# trackuino_micro_sensor.net
KiCad netlist of a schematic drawn in EAGLE
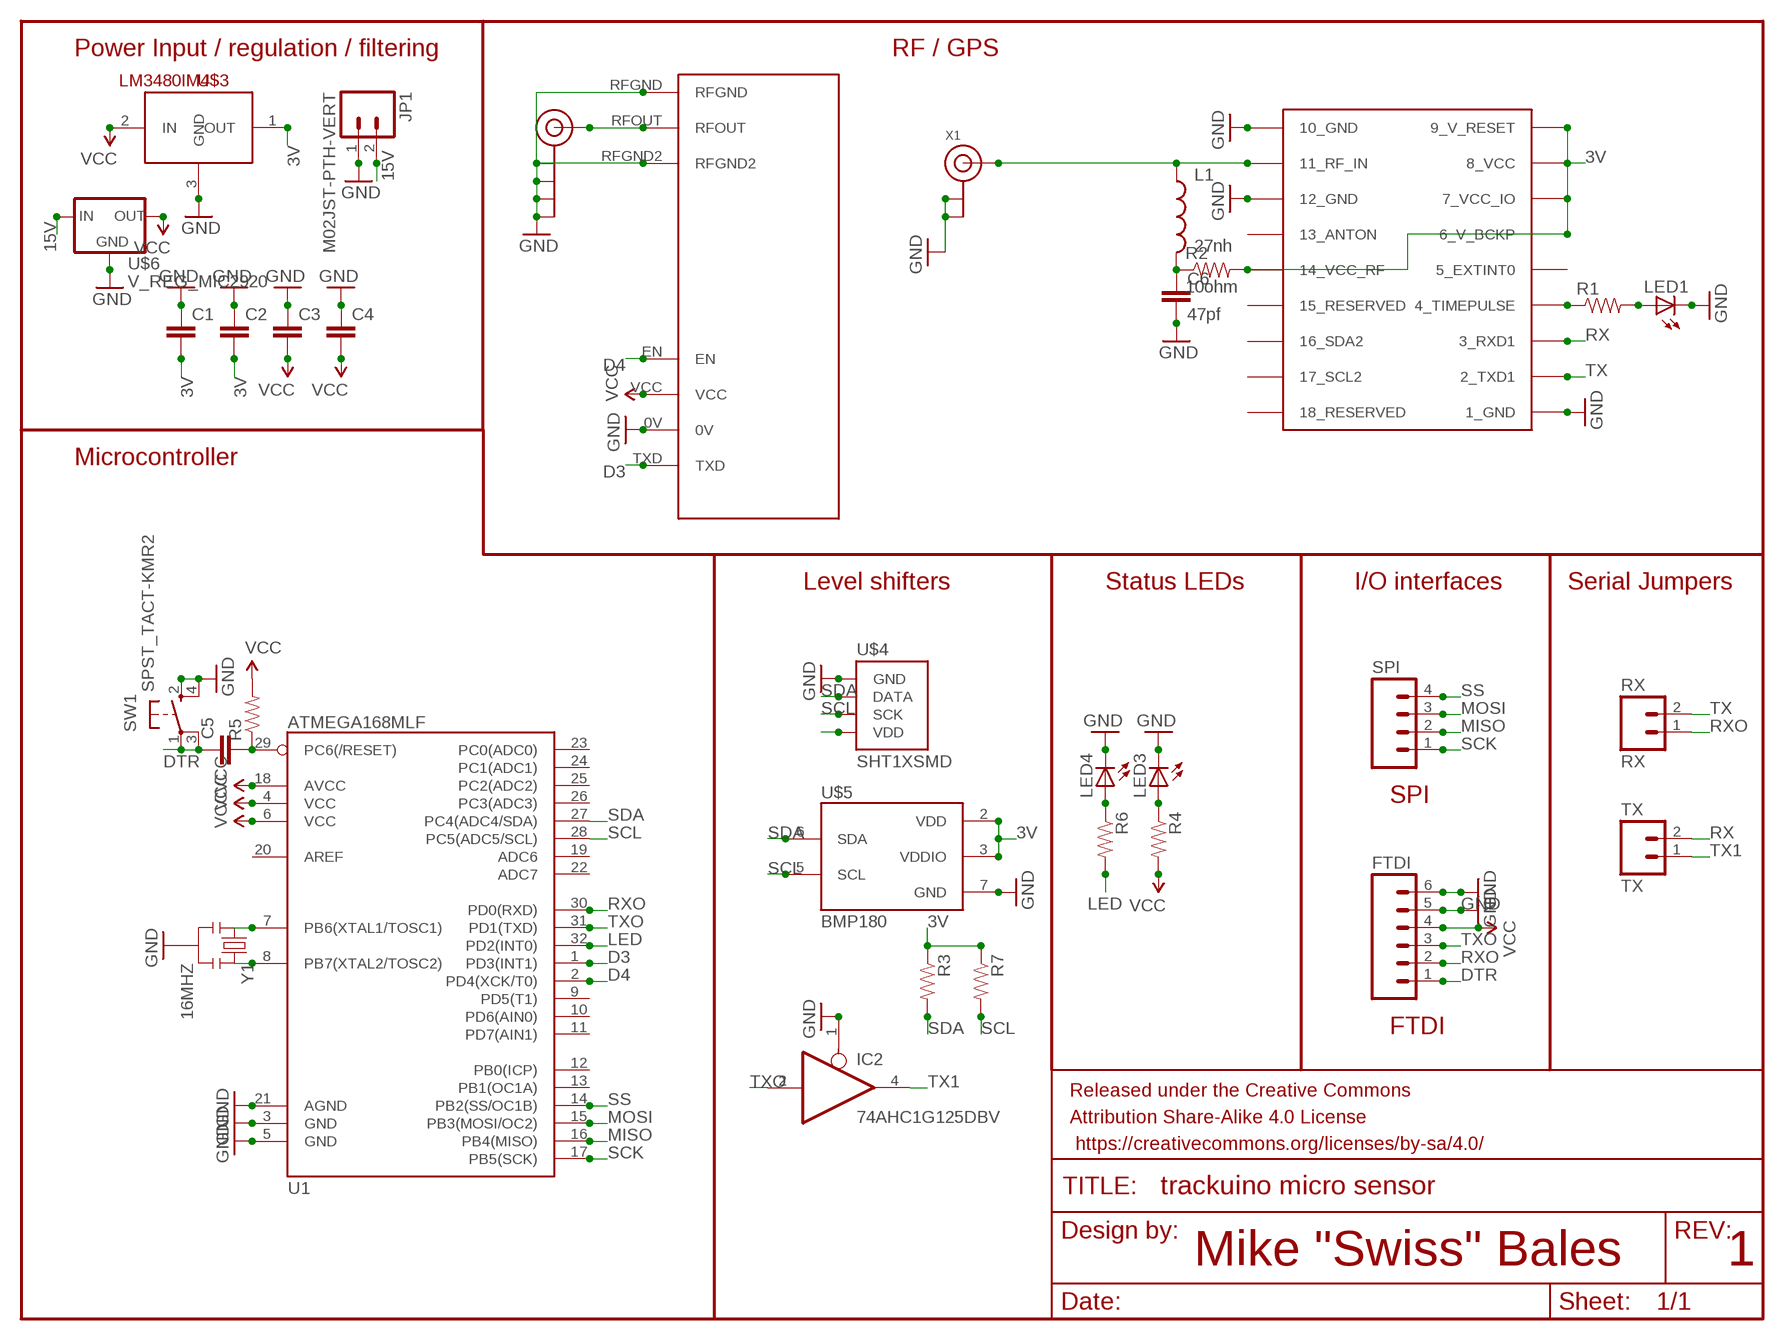
[diagram p0: schematic, sheet 1]

(export (version "E")
  (design (tool "Eeschema 10.0.6"))
  (components
    (comp (ref "C1")
      (value "CAP0805")
      (footprint "eagle-import:0805")
      (libsource (lib "eagle-import") (part "CAP0805"))
    )
    (comp (ref "C2")
      (value "CAP0805")
      (footprint "eagle-import:0805")
      (libsource (lib "eagle-import") (part "CAP0805"))
    )
    (comp (ref "C3")
      (value "CAP0805")
      (footprint "eagle-import:0805")
      (libsource (lib "eagle-import") (part "CAP0805"))
    )
    (comp (ref "C4")
      (value "CAP0805")
      (footprint "eagle-import:0805")
      (libsource (lib "eagle-import") (part "CAP0805"))
    )
    (comp (ref "C5")
      (value "CAP0805")
      (footprint "eagle-import:0805")
      (libsource (lib "eagle-import") (part "CAP0805"))
    )
    (comp (ref "C6")
      (value "47pf")
      (footprint "eagle-import:0805")
      (libsource (lib "eagle-import") (part "CAP0805"))
    )
    (comp (ref "FRAME1")
      (value "FRAME-LETTER")
      (footprint "eagle-import:CREATIVE_COMMONS")
      (libsource (lib "eagle-import") (part "FRAME-LETTER"))
    )
    (comp (ref "FTDI")
      (value "M06NO_SILK_FEMALE_PTH")
      (footprint "eagle-import:1X06_NO_SILK")
      (libsource (lib "eagle-import") (part "M06NO_SILK_FEMALE_PTH"))
    )
    (comp (ref "IC2")
      (value "74AHC1G125DBV")
      (footprint "eagle-import:SOT23-5")
      (libsource (lib "eagle-import") (part "741G125DBVAHC"))
    )
    (comp (ref "J$1")
      (value "SMA_EDGE")
      (footprint "eagle-import:SMA-EDGE")
      (libsource (lib "eagle-import") (part "SMA_EDGE"))
    )
    (comp (ref "JP1")
      (value "M02JST-PTH-VERT")
      (footprint "eagle-import:JST-2-PTH-VERT")
      (libsource (lib "eagle-import") (part "M02JST-PTH-VERT"))
    )
    (comp (ref "L1")
      (value "27nh")
      (footprint "eagle-import:0805")
      (libsource (lib "eagle-import") (part "INDUCTOR0805"))
    )
    (comp (ref "LED1")
      (value "LEDCHIP-LED0805")
      (footprint "eagle-import:CHIP-LED0805")
      (libsource (lib "eagle-import") (part "LEDCHIP-LED0805"))
    )
    (comp (ref "LED3")
      (value "LEDCHIP-LED0805")
      (footprint "eagle-import:CHIP-LED0805")
      (libsource (lib "eagle-import") (part "LEDCHIP-LED0805"))
    )
    (comp (ref "LED4")
      (value "LEDCHIP-LED0805")
      (footprint "eagle-import:CHIP-LED0805")
      (libsource (lib "eagle-import") (part "LEDCHIP-LED0805"))
    )
    (comp (ref "R1")
      (value "RESISTOR0805-RES")
      (footprint "eagle-import:0805")
      (libsource (lib "eagle-import") (part "RESISTOR0805-RES"))
    )
    (comp (ref "R2")
      (value "10ohm")
      (footprint "eagle-import:0805")
      (libsource (lib "eagle-import") (part "RESISTOR0805-RES"))
    )
    (comp (ref "R3")
      (value "RESISTOR0805-RES")
      (footprint "eagle-import:0805")
      (libsource (lib "eagle-import") (part "RESISTOR0805-RES"))
    )
    (comp (ref "R4")
      (value "RESISTOR0805-RES")
      (footprint "eagle-import:0805")
      (libsource (lib "eagle-import") (part "RESISTOR0805-RES"))
    )
    (comp (ref "R5")
      (value "RESISTOR0805-RES")
      (footprint "eagle-import:0805")
      (libsource (lib "eagle-import") (part "RESISTOR0805-RES"))
    )
    (comp (ref "R6")
      (value "RESISTOR0805-RES")
      (footprint "eagle-import:0805")
      (libsource (lib "eagle-import") (part "RESISTOR0805-RES"))
    )
    (comp (ref "R7")
      (value "RESISTOR0805-RES")
      (footprint "eagle-import:0805")
      (libsource (lib "eagle-import") (part "RESISTOR0805-RES"))
    )
    (comp (ref "RX")
      (value "RX")
      (footprint "eagle-import:1X02")
      (libsource (lib "eagle-import") (part "M02PTH"))
    )
    (comp (ref "SPI")
      (value "M041X04_NO_SILK")
      (footprint "eagle-import:1X04_NO_SILK")
      (libsource (lib "eagle-import") (part "M041X04_NO_SILK"))
    )
    (comp (ref "SW1")
      (value "SPST_TACT-KMR2")
      (footprint "eagle-import:KMR2")
      (libsource (lib "eagle-import") (part "SPST_TACT-KMR2"))
    )
    (comp (ref "TX")
      (value "TX")
      (footprint "eagle-import:1X02")
      (libsource (lib "eagle-import") (part "M02PTH"))
    )
    (comp (ref "U$1")
      (value "UBLOX_MAX")
      (footprint "eagle-import:UBLOX_MAX")
      (libsource (lib "eagle-import") (part "UBLOX_MAX"))
    )
    (comp (ref "U$2")
      (value "RADIOMETRIX-HX1")
      (footprint "eagle-import:RADIOMETRIX-HX1")
      (libsource (lib "eagle-import") (part "RADIOMETRIX-HX1"))
    )
    (comp (ref "U$3")
      (value "LM3480IM4")
      (footprint "eagle-import:SOT23-3")
      (libsource (lib "eagle-import") (part "LM3480IM4"))
    )
    (comp (ref "U$4")
      (value "SHT1XSMD")
      (footprint "eagle-import:SHT1X")
      (libsource (lib "eagle-import") (part "SHT1XSMD"))
    )
    (comp (ref "U$5")
      (value "BMP180")
      (footprint "eagle-import:BMP180")
      (libsource (lib "eagle-import") (part "BMP180"))
    )
    (comp (ref "U$6")
      (value "V_REG_MIC2920")
      (footprint "eagle-import:SOT223")
      (libsource (lib "eagle-import") (part "V_REG_MIC2920"))
    )
    (comp (ref "U1")
      (value "ATMEGA168MLF")
      (footprint "eagle-import:MLF32")
      (libsource (lib "eagle-import") (part "ATMEGA168MLF"))
    )
    (comp (ref "X1")
      (value "ANTENNA_U.FL")
      (footprint "eagle-import:U.FL")
      (libsource (lib "eagle-import") (part "ANTENNA_U.FL"))
    )
    (comp (ref "Y1")
      (value "16MHZ")
      (footprint "eagle-import:RESONATOR-SMD")
      (libsource (lib "eagle-import") (part "RESONATOR16MHZ"))
    )
  )
  (nets
    (net (code "1") (name "/3V") (class "Default")
      (node (ref "C1") (pin "2") (pinfunction "2_2") (pintype "passive"))
      (node (ref "C2") (pin "2") (pinfunction "2_2") (pintype "passive"))
      (node (ref "R2") (pin "2") (pinfunction "2_2") (pintype "passive"))
      (node (ref "R3") (pin "1") (pinfunction "1_1") (pintype "passive"))
      (node (ref "R7") (pin "1") (pinfunction "1_1") (pintype "passive"))
      (node (ref "U$1") (pin "14_VCC_RF") (pinfunction "14_VCC_RF_14_VCC_RF") (pintype "bidirectional"))
      (node (ref "U$1") (pin "6_V_BCKP") (pinfunction "6_V_BCKP_6_V_BCKP") (pintype "bidirectional"))
      (node (ref "U$1") (pin "7_VCC_IO") (pinfunction "7_VCC_IO_7_VCC_IO") (pintype "power_in"))
      (node (ref "U$1") (pin "8_VCC") (pinfunction "8_VCC_8_VCC") (pintype "power_in"))
      (node (ref "U$1") (pin "9_V_RESET") (pinfunction "9_V_RESET_9_V_RESET") (pintype "power_in"))
      (node (ref "U$3") (pin "1") (pinfunction "OUT_1") (pintype "bidirectional"))
      (node (ref "U$4") (pin "4") (pinfunction "VDD_4") (pintype "power_in"))
      (node (ref "U$5") (pin "2") (pinfunction "VDD_2") (pintype "power_in"))
      (node (ref "U$5") (pin "3") (pinfunction "VDDIO_3") (pintype "power_in"))
    )
    (net (code "2") (name "/15V") (class "Default")
      (node (ref "JP1") (pin "2") (pinfunction "2_2") (pintype "passive"))
      (node (ref "U$6") (pin "1") (pinfunction "IN_1") (pintype "input"))
    )
    (net (code "3") (name "/D3") (class "Default")
      (node (ref "U$2") (pin "TXD") (pinfunction "TXD_TXD") (pintype "bidirectional"))
      (node (ref "U1") (pin "1") (pinfunction "PD3(INT1)_1") (pintype "bidirectional"))
    )
    (net (code "4") (name "/D4") (class "Default")
      (node (ref "U$2") (pin "EN") (pinfunction "EN_EN") (pintype "bidirectional"))
      (node (ref "U1") (pin "2") (pinfunction "PD4(XCK/T0)_2") (pintype "bidirectional"))
    )
    (net (code "5") (name "/DTR") (class "Default")
      (node (ref "C5") (pin "1") (pinfunction "1_1") (pintype "passive"))
      (node (ref "FTDI") (pin "1") (pinfunction "1_1") (pintype "passive"))
      (node (ref "SW1") (pin "1") (pinfunction "P_1") (pintype "passive"))
      (node (ref "SW1") (pin "3") (pinfunction "P1_3") (pintype "passive"))
    )
    (net (code "6") (name "/LED") (class "Default")
      (node (ref "R6") (pin "2") (pinfunction "2_2") (pintype "passive"))
      (node (ref "U1") (pin "32") (pinfunction "PD2(INT0)_32") (pintype "bidirectional"))
    )
    (net (code "7") (name "/MISO") (class "Default")
      (node (ref "SPI") (pin "2") (pinfunction "2_2") (pintype "passive"))
      (node (ref "U1") (pin "16") (pinfunction "PB4(MISO)_16") (pintype "bidirectional"))
    )
    (net (code "8") (name "/MOSI") (class "Default")
      (node (ref "SPI") (pin "3") (pinfunction "3_3") (pintype "passive"))
      (node (ref "U1") (pin "15") (pinfunction "PB3(MOSI/OC2)_15") (pintype "bidirectional"))
    )
    (net (code "9") (name "/RX") (class "Default")
      (node (ref "TX") (pin "2") (pinfunction "2_2") (pintype "passive"))
      (node (ref "U$1") (pin "3_RXD1") (pinfunction "3_RXD1_3_RXD1") (pintype "bidirectional"))
    )
    (net (code "10") (name "/RXO") (class "Default")
      (node (ref "FTDI") (pin "2") (pinfunction "2_2") (pintype "passive"))
      (node (ref "RX") (pin "1") (pinfunction "1_1") (pintype "passive"))
      (node (ref "U1") (pin "30") (pinfunction "PD0(RXD)_30") (pintype "bidirectional"))
    )
    (net (code "11") (name "/SCK") (class "Default")
      (node (ref "SPI") (pin "1") (pinfunction "1_1") (pintype "passive"))
      (node (ref "U1") (pin "17") (pinfunction "PB5(SCK)_17") (pintype "bidirectional"))
    )
    (net (code "12") (name "/SCL") (class "Default")
      (node (ref "R7") (pin "2") (pinfunction "2_2") (pintype "passive"))
      (node (ref "U$4") (pin "3") (pinfunction "SCK_3") (pintype "input"))
      (node (ref "U$5") (pin "5") (pinfunction "SCL_5") (pintype "input"))
      (node (ref "U1") (pin "28") (pinfunction "PC5(ADC5/SCL)_28") (pintype "bidirectional"))
    )
    (net (code "13") (name "/SDA") (class "Default")
      (node (ref "R3") (pin "2") (pinfunction "2_2") (pintype "passive"))
      (node (ref "U$4") (pin "2") (pinfunction "DATA_2") (pintype "bidirectional"))
      (node (ref "U$5") (pin "6") (pinfunction "SDA_6") (pintype "bidirectional"))
      (node (ref "U1") (pin "27") (pinfunction "PC4(ADC4/SDA)_27") (pintype "bidirectional"))
    )
    (net (code "14") (name "/SS") (class "Default")
      (node (ref "SPI") (pin "4") (pinfunction "4_4") (pintype "passive"))
      (node (ref "U1") (pin "14") (pinfunction "PB2(SS/OC1B)_14") (pintype "bidirectional"))
    )
    (net (code "15") (name "/TX") (class "Default")
      (node (ref "RX") (pin "2") (pinfunction "2_2") (pintype "passive"))
      (node (ref "U$1") (pin "2_TXD1") (pinfunction "2_TXD1_2_TXD1") (pintype "bidirectional"))
    )
    (net (code "16") (name "/TX1") (class "Default")
      (node (ref "IC2") (pin "4") (pinfunction "O_4") (pintype "tri_state"))
      (node (ref "TX") (pin "1") (pinfunction "1_1") (pintype "passive"))
    )
    (net (code "17") (name "/TXO") (class "Default")
      (node (ref "FTDI") (pin "3") (pinfunction "3_3") (pintype "passive"))
      (node (ref "IC2") (pin "2") (pinfunction "I_2") (pintype "input"))
      (node (ref "U1") (pin "31") (pinfunction "PD1(TXD)_31") (pintype "bidirectional"))
    )
    (net (code "18") (name "GND") (class "Default")
      (node (ref "C1") (pin "1") (pinfunction "1_1") (pintype "passive"))
      (node (ref "C2") (pin "1") (pinfunction "1_1") (pintype "passive"))
      (node (ref "C3") (pin "1") (pinfunction "1_1") (pintype "passive"))
      (node (ref "C4") (pin "1") (pinfunction "1_1") (pintype "passive"))
      (node (ref "C6") (pin "2") (pinfunction "2_2") (pintype "passive"))
      (node (ref "FTDI") (pin "5") (pinfunction "5_5") (pintype "passive"))
      (node (ref "FTDI") (pin "6") (pinfunction "6_6") (pintype "passive"))
      (node (ref "IC2") (pin "1") (pinfunction "OE_1") (pintype "input"))
      (node (ref "J$1") (pin "GND@0") (pinfunction "GND_GND@0") (pintype "bidirectional"))
      (node (ref "J$1") (pin "GND@1") (pinfunction "GND_GND@1") (pintype "bidirectional"))
      (node (ref "J$1") (pin "GND@2") (pinfunction "GND_GND@2") (pintype "bidirectional"))
      (node (ref "J$1") (pin "GND@3") (pinfunction "GND_GND@3") (pintype "bidirectional"))
      (node (ref "JP1") (pin "1") (pinfunction "1_1") (pintype "passive"))
      (node (ref "LED1") (pin "C") (pinfunction "C_C") (pintype "passive"))
      (node (ref "LED3") (pin "C") (pinfunction "C_C") (pintype "passive"))
      (node (ref "LED4") (pin "C") (pinfunction "C_C") (pintype "passive"))
      (node (ref "SW1") (pin "2") (pinfunction "S_2") (pintype "passive"))
      (node (ref "SW1") (pin "4") (pinfunction "S1_4") (pintype "passive"))
      (node (ref "U$1") (pin "10_GND") (pinfunction "10_GND_10_GND") (pintype "power_in"))
      (node (ref "U$1") (pin "12_GND") (pinfunction "12_GND_12_GND") (pintype "power_in"))
      (node (ref "U$1") (pin "1_GND") (pinfunction "1_GND_1_GND") (pintype "power_in"))
      (node (ref "U$2") (pin "0V") (pinfunction "0V_0V") (pintype "bidirectional"))
      (node (ref "U$2") (pin "RFGND") (pinfunction "RFGND_RFGND") (pintype "bidirectional"))
      (node (ref "U$2") (pin "RFGND2") (pinfunction "RFGND2_RFGND2") (pintype "bidirectional"))
      (node (ref "U$3") (pin "3") (pinfunction "GND_3") (pintype "bidirectional"))
      (node (ref "U$4") (pin "1") (pinfunction "GND_1") (pintype "power_in"))
      (node (ref "U$5") (pin "7") (pinfunction "GND_7") (pintype "power_in"))
      (node (ref "U$6") (pin "2") (pinfunction "GND_2") (pintype "input"))
      (node (ref "U1") (pin "21") (pinfunction "AGND_21") (pintype "bidirectional"))
      (node (ref "U1") (pin "3") (pinfunction "GND_3") (pintype "bidirectional"))
      (node (ref "U1") (pin "5") (pinfunction "GND_5") (pintype "bidirectional"))
      (node (ref "X1") (pin "1") (pinfunction "GND_1") (pintype "passive"))
      (node (ref "X1") (pin "2") (pinfunction "GND_2") (pintype "passive"))
      (node (ref "Y1") (pin "2") (pinfunction "2_2") (pintype "passive"))
    )
    (net (code "19") (name "Net-(C6-Pad1)") (class "Default")
      (node (ref "C6") (pin "1") (pinfunction "1_1") (pintype "passive"))
      (node (ref "L1") (pin "2") (pinfunction "2_2") (pintype "passive"))
      (node (ref "R2") (pin "1") (pinfunction "1_1") (pintype "passive"))
    )
    (net (code "20") (name "Net-(J$1-SIGNAL)") (class "Default")
      (node (ref "J$1") (pin "SIG") (pinfunction "SIGNAL_SIG") (pintype "bidirectional"))
      (node (ref "U$2") (pin "RFOUT") (pinfunction "RFOUT_RFOUT") (pintype "bidirectional"))
    )
    (net (code "21") (name "Net-(LED1-PadA)") (class "Default")
      (node (ref "LED1") (pin "A") (pinfunction "A_A") (pintype "passive"))
      (node (ref "R1") (pin "2") (pinfunction "2_2") (pintype "passive"))
    )
    (net (code "22") (name "Net-(LED3-PadA)") (class "Default")
      (node (ref "LED3") (pin "A") (pinfunction "A_A") (pintype "passive"))
      (node (ref "R4") (pin "1") (pinfunction "1_1") (pintype "passive"))
    )
    (net (code "23") (name "Net-(LED4-PadA)") (class "Default")
      (node (ref "LED4") (pin "A") (pinfunction "A_A") (pintype "passive"))
      (node (ref "R6") (pin "1") (pinfunction "1_1") (pintype "passive"))
    )
    (net (code "24") (name "Net-(R1-Pad1)") (class "Default")
      (node (ref "R1") (pin "1") (pinfunction "1_1") (pintype "passive"))
      (node (ref "U$1") (pin "4_TIMEPULSE") (pinfunction "4_TIMEPULSE_4_TIMEPULSE") (pintype "bidirectional"))
    )
    (net (code "25") (name "Net-(U1-PB6(XTAL1{slash}TOSC1))") (class "Default")
      (node (ref "U1") (pin "7") (pinfunction "PB6(XTAL1/TOSC1)_7") (pintype "bidirectional"))
      (node (ref "Y1") (pin "1") (pinfunction "1_1") (pintype "passive"))
    )
    (net (code "26") (name "Net-(U1-PB7(XTAL2{slash}TOSC2))") (class "Default")
      (node (ref "U1") (pin "8") (pinfunction "PB7(XTAL2/TOSC2)_8") (pintype "bidirectional"))
      (node (ref "Y1") (pin "3") (pinfunction "3_3") (pintype "passive"))
    )
    (net (code "27") (name "Net-(U1-PC6({slash}RESET))") (class "Default")
      (node (ref "C5") (pin "2") (pinfunction "2_2") (pintype "passive"))
      (node (ref "R5") (pin "1") (pinfunction "1_1") (pintype "passive"))
      (node (ref "U1") (pin "29") (pinfunction "PC6(/RESET)_29") (pintype "bidirectional"))
    )
    (net (code "28") (name "Net-(X1-SIGNAL)") (class "Default")
      (node (ref "L1") (pin "1") (pinfunction "1_1") (pintype "passive"))
      (node (ref "U$1") (pin "11_RF_IN") (pinfunction "11_RF_IN_11_RF_IN") (pintype "bidirectional"))
      (node (ref "X1") (pin "3") (pinfunction "SIGNAL_3") (pintype "passive"))
    )
    (net (code "29") (name "VCC") (class "Default")
      (node (ref "C3") (pin "2") (pinfunction "2_2") (pintype "passive"))
      (node (ref "C4") (pin "2") (pinfunction "2_2") (pintype "passive"))
      (node (ref "FTDI") (pin "4") (pinfunction "4_4") (pintype "passive"))
      (node (ref "R4") (pin "2") (pinfunction "2_2") (pintype "passive"))
      (node (ref "R5") (pin "2") (pinfunction "2_2") (pintype "passive"))
      (node (ref "U$2") (pin "VCC") (pinfunction "VCC_VCC") (pintype "bidirectional"))
      (node (ref "U$3") (pin "2") (pinfunction "IN_2") (pintype "bidirectional"))
      (node (ref "U$6") (pin "3") (pinfunction "OUT_3") (pintype "output"))
      (node (ref "U1") (pin "18") (pinfunction "AVCC_18") (pintype "bidirectional"))
      (node (ref "U1") (pin "4") (pinfunction "VCC_4") (pintype "bidirectional"))
      (node (ref "U1") (pin "6") (pinfunction "VCC_6") (pintype "bidirectional"))
    )
    (net (code "30") (name "unconnected-(U$1-Pad5_EXTINT0)") (class "Default")
      (node (ref "U$1") (pin "5_EXTINT0") (pinfunction "5_EXTINT0_5_EXTINT0") (pintype "bidirectional"))
    )
    (net (code "31") (name "unconnected-(U$1-Pad13_ANTON)") (class "Default")
      (node (ref "U$1") (pin "13_ANTON") (pinfunction "13_ANTON_13_ANTON") (pintype "bidirectional"))
    )
    (net (code "32") (name "unconnected-(U$1-Pad15_RESERVED)") (class "Default")
      (node (ref "U$1") (pin "15_RESERVED") (pinfunction "15_RESERVED_15_RESERVED") (pintype "bidirectional"))
    )
    (net (code "33") (name "unconnected-(U$1-Pad16_SDA2)") (class "Default")
      (node (ref "U$1") (pin "16_SDA2") (pinfunction "16_SDA2_16_SDA2") (pintype "bidirectional"))
    )
    (net (code "34") (name "unconnected-(U$1-Pad17_SCL2)") (class "Default")
      (node (ref "U$1") (pin "17_SCL2") (pinfunction "17_SCL2_17_SCL2") (pintype "bidirectional"))
    )
    (net (code "35") (name "unconnected-(U$1-Pad18_RESERVED)") (class "Default")
      (node (ref "U$1") (pin "18_RESERVED") (pinfunction "18_RESERVED_18_RESERVED") (pintype "bidirectional"))
    )
    (net (code "36") (name "unconnected-(U1-ADC6-Pad19)") (class "Default")
      (node (ref "U1") (pin "19") (pinfunction "ADC6_19") (pintype "bidirectional"))
    )
    (net (code "37") (name "unconnected-(U1-ADC7-Pad22)") (class "Default")
      (node (ref "U1") (pin "22") (pinfunction "ADC7_22") (pintype "bidirectional"))
    )
    (net (code "38") (name "unconnected-(U1-AREF-Pad20)") (class "Default")
      (node (ref "U1") (pin "20") (pinfunction "AREF_20") (pintype "bidirectional"))
    )
    (net (code "39") (name "unconnected-(U1-PB0(ICP)-Pad12)") (class "Default")
      (node (ref "U1") (pin "12") (pinfunction "PB0(ICP)_12") (pintype "bidirectional"))
    )
    (net (code "40") (name "unconnected-(U1-PB1(OC1A)-Pad13)") (class "Default")
      (node (ref "U1") (pin "13") (pinfunction "PB1(OC1A)_13") (pintype "bidirectional"))
    )
    (net (code "41") (name "unconnected-(U1-PC0(ADC0)-Pad23)") (class "Default")
      (node (ref "U1") (pin "23") (pinfunction "PC0(ADC0)_23") (pintype "bidirectional"))
    )
    (net (code "42") (name "unconnected-(U1-PC1(ADC1)-Pad24)") (class "Default")
      (node (ref "U1") (pin "24") (pinfunction "PC1(ADC1)_24") (pintype "bidirectional"))
    )
    (net (code "43") (name "unconnected-(U1-PC2(ADC2)-Pad25)") (class "Default")
      (node (ref "U1") (pin "25") (pinfunction "PC2(ADC2)_25") (pintype "bidirectional"))
    )
    (net (code "44") (name "unconnected-(U1-PC3(ADC3)-Pad26)") (class "Default")
      (node (ref "U1") (pin "26") (pinfunction "PC3(ADC3)_26") (pintype "bidirectional"))
    )
    (net (code "45") (name "unconnected-(U1-PD5(T1)-Pad9)") (class "Default")
      (node (ref "U1") (pin "9") (pinfunction "PD5(T1)_9") (pintype "bidirectional"))
    )
    (net (code "46") (name "unconnected-(U1-PD6(AIN0)-Pad10)") (class "Default")
      (node (ref "U1") (pin "10") (pinfunction "PD6(AIN0)_10") (pintype "bidirectional"))
    )
    (net (code "47") (name "unconnected-(U1-PD7(AIN1)-Pad11)") (class "Default")
      (node (ref "U1") (pin "11") (pinfunction "PD7(AIN1)_11") (pintype "bidirectional"))
    )
  )
)
